# POWER.net
KiCad netlist of a schematic drawn in Altium Designer
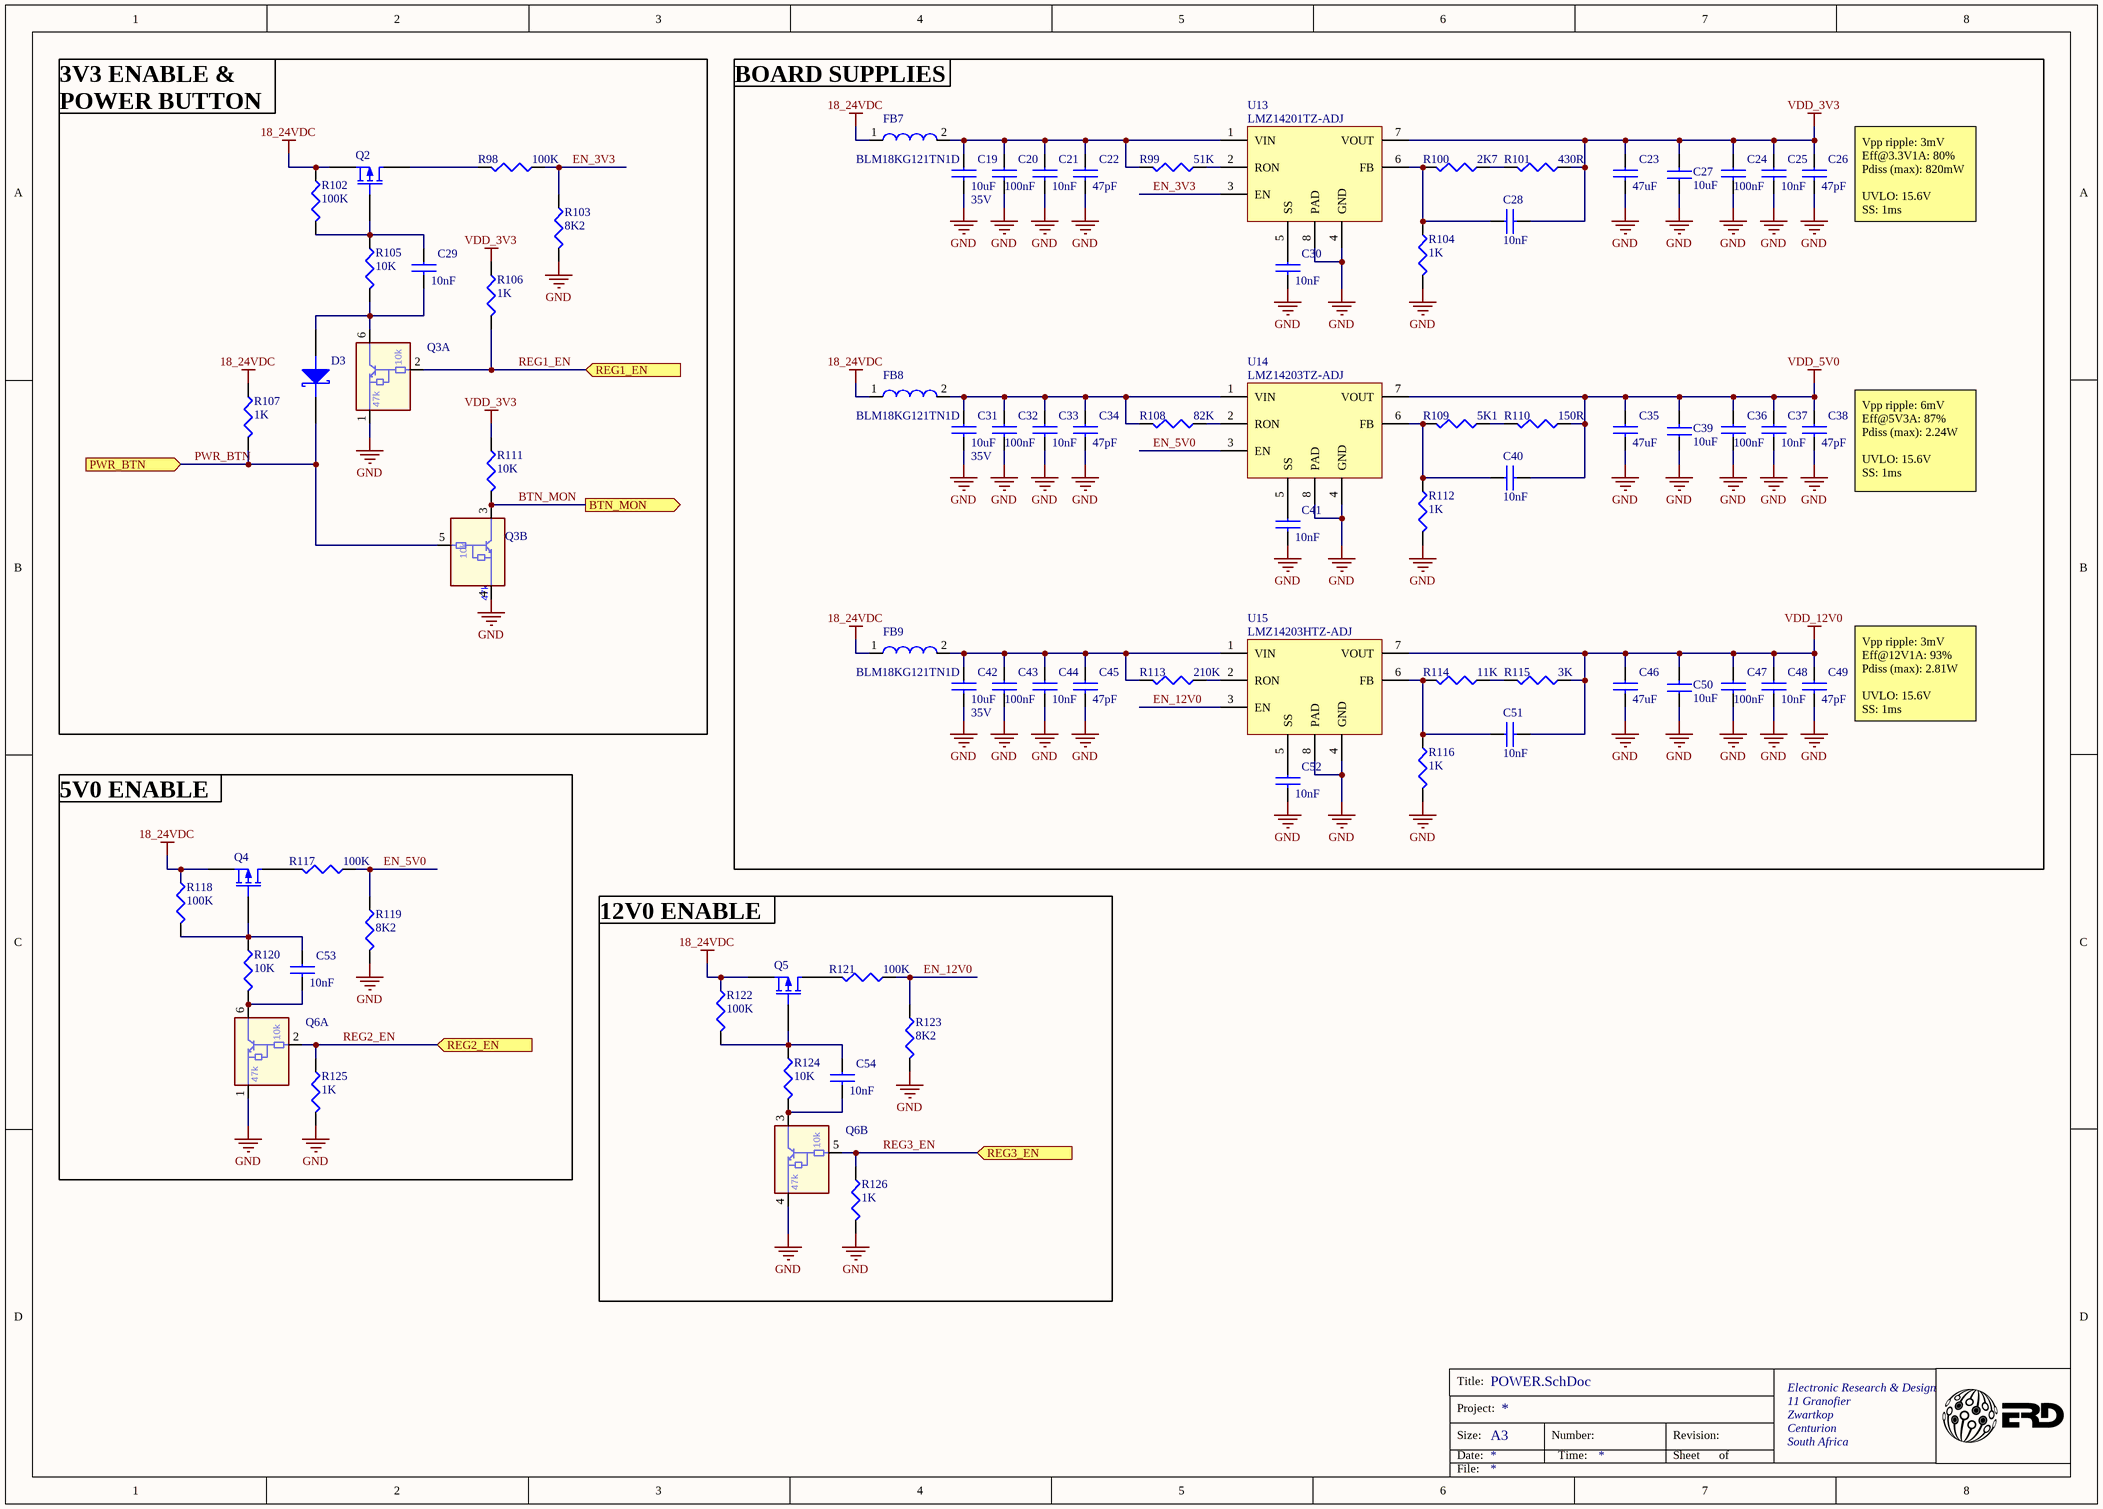
[diagram p0: POWER.SchDoc]

(export (version "E")
  (design (tool "Eeschema 10.0.6"))
  (components
    (comp (ref "C19")
      (value "10uF")
      (footprint "CC0805")
      (description "CAP CER 10UF 35V 10% X5R 0805")
      (fields
        (field (name "MANUFACTURER") "Murata")
        (field (name "PART NUMBER") "GRM21BR6YA106KE43L")
        (field (name "VOLTAGE RATING") "35V")
      )
      (libsource (lib "ERD TiAm") (part "CAP CER 0.1UF 10V 10% X5R 0402"))
    )
    (comp (ref "C20")
      (value "100nF")
      (footprint "CC0402")
      (description "CAP CER 0.1UF 50V 10% X7R 0402")
      (fields (field (name "MANUFACTURER") "Murata") (field (name "PART NUMBER") "GCM155R71H104KE02D"))
      (libsource (lib "ERD TiAm") (part "CAP CER 0.1UF 10V 10% X5R 0402"))
    )
    (comp (ref "C21")
      (value "10nF")
      (footprint "CC0402")
      (description "CAP CER 10NF 50V 10% X7R 0402")
      (fields (field (name "MANUFACTURER") "Murata") (field (name "PART NUMBER") "GRM155R71H103KA88J"))
      (libsource (lib "ERD TiAm") (part "CAP CER 0.1UF 10V 10% X5R 0402"))
    )
    (comp (ref "C22")
      (value "47pF")
      (footprint "CC0402")
      (description "CAP CER 47PF 50V 5% C0G/NP0 0402")
      (fields (field (name "MANUFACTURER") "Murata") (field (name "PART NUMBER") "GCM1555C1H470JA16D"))
      (libsource (lib "ERD TiAm") (part "CAP CER 0.1UF 10V 10% X5R 0402"))
    )
    (comp (ref "C23")
      (value "47uF")
      (footprint "RC1206")
      (description "CAP CER 47UF 25V 20% X5R 1206")
      (fields (field (name "MANUFACTURER") "Murata") (field (name "PART NUMBER") "C3216X5R1E476M160AC"))
      (libsource (lib "ERD TiAm") (part "CAP CER 0.1UF 10V 10% X5R 0402"))
    )
    (comp (ref "C24")
      (value "100nF")
      (footprint "CC0402")
      (description "CAP CER 0.1UF 50V 10% X7R 0402")
      (fields (field (name "MANUFACTURER") "Murata") (field (name "PART NUMBER") "GCM155R71H104KE02D"))
      (libsource (lib "ERD TiAm") (part "CAP CER 0.1UF 10V 10% X5R 0402"))
    )
    (comp (ref "C25")
      (value "10nF")
      (footprint "CC0402")
      (description "CAP CER 10NF 50V 10% X7R 0402")
      (fields (field (name "MANUFACTURER") "Murata") (field (name "PART NUMBER") "GRM155R71H103KA88J"))
      (libsource (lib "ERD TiAm") (part "CAP CER 0.1UF 10V 10% X5R 0402"))
    )
    (comp (ref "C26")
      (value "47pF")
      (footprint "CC0402")
      (description "CAP CER 47PF 50V 5% C0G/NP0 0402")
      (fields (field (name "MANUFACTURER") "Murata") (field (name "PART NUMBER") "GCM1555C1H470JA16D"))
      (libsource (lib "ERD TiAm") (part "CAP CER 0.1UF 10V 10% X5R 0402"))
    )
    (comp (ref "C27")
      (value "10uF")
      (footprint "CC0603")
      (description "CAP CER 10UF 25V 20% X5R 0603")
      (fields (field (name "MANUFACTURER") "Murata") (field (name "PARTNUMBER") "GRM188R61E106MA73D"))
      (libsource (lib "ERD TiAm") (part "CAP CER 0.1UF 10V 10% X5R 0402"))
    )
    (comp (ref "C28")
      (value "10nF")
      (footprint "CC0402")
      (description "CAP CER 10NF 50V 10% X7R 0402")
      (fields (field (name "MANUFACTURER") "Murata") (field (name "PART NUMBER") "GRM155R71H103KA88J"))
      (libsource (lib "ERD TiAm") (part "CAP CER 0.1UF 10V 10% X5R 0402"))
    )
    (comp (ref "C29")
      (value "10nF")
      (footprint "CC0402")
      (description "CAP CER 10NF 50V 10% X7R 0402")
      (fields (field (name "MANUFACTURER") "Murata") (field (name "PART NUMBER") "GRM155R71H103KA88J"))
      (libsource (lib "ERD TiAm") (part "CAP CER 0.1UF 10V 10% X5R 0402"))
    )
    (comp (ref "C30")
      (value "10nF")
      (footprint "CC0402")
      (description "CAP CER 10NF 50V 10% X7R 0402")
      (fields (field (name "MANUFACTURER") "Murata") (field (name "PART NUMBER") "GRM155R71H103KA88J"))
      (libsource (lib "ERD TiAm") (part "CAP CER 0.1UF 10V 10% X5R 0402"))
    )
    (comp (ref "C31")
      (value "10uF")
      (footprint "CC0805")
      (description "CAP CER 10UF 35V 10% X5R 0805")
      (fields
        (field (name "MANUFACTURER") "Murata")
        (field (name "PART NUMBER") "GRM21BR6YA106KE43L")
        (field (name "VOLTAGE RATING") "35V")
      )
      (libsource (lib "ERD TiAm") (part "CAP CER 0.1UF 10V 10% X5R 0402"))
    )
    (comp (ref "C32")
      (value "100nF")
      (footprint "CC0402")
      (description "CAP CER 0.1UF 50V 10% X7R 0402")
      (fields (field (name "MANUFACTURER") "Murata") (field (name "PART NUMBER") "GCM155R71H104KE02D"))
      (libsource (lib "ERD TiAm") (part "CAP CER 0.1UF 10V 10% X5R 0402"))
    )
    (comp (ref "C33")
      (value "10nF")
      (footprint "CC0402")
      (description "CAP CER 10NF 50V 10% X7R 0402")
      (fields (field (name "MANUFACTURER") "Murata") (field (name "PART NUMBER") "GRM155R71H103KA88J"))
      (libsource (lib "ERD TiAm") (part "CAP CER 0.1UF 10V 10% X5R 0402"))
    )
    (comp (ref "C34")
      (value "47pF")
      (footprint "CC0402")
      (description "CAP CER 47PF 50V 5% C0G/NP0 0402")
      (fields (field (name "MANUFACTURER") "Murata") (field (name "PART NUMBER") "GCM1555C1H470JA16D"))
      (libsource (lib "ERD TiAm") (part "CAP CER 0.1UF 10V 10% X5R 0402"))
    )
    (comp (ref "C35")
      (value "47uF")
      (footprint "RC1206")
      (description "CAP CER 47UF 25V 20% X5R 1206")
      (fields (field (name "MANUFACTURER") "Murata") (field (name "PART NUMBER") "C3216X5R1E476M160AC"))
      (libsource (lib "ERD TiAm") (part "CAP CER 0.1UF 10V 10% X5R 0402"))
    )
    (comp (ref "C36")
      (value "100nF")
      (footprint "CC0402")
      (description "CAP CER 0.1UF 50V 10% X7R 0402")
      (fields (field (name "MANUFACTURER") "Murata") (field (name "PART NUMBER") "GCM155R71H104KE02D"))
      (libsource (lib "ERD TiAm") (part "CAP CER 0.1UF 10V 10% X5R 0402"))
    )
    (comp (ref "C37")
      (value "10nF")
      (footprint "CC0402")
      (description "CAP CER 10NF 50V 10% X7R 0402")
      (fields (field (name "MANUFACTURER") "Murata") (field (name "PART NUMBER") "GRM155R71H103KA88J"))
      (libsource (lib "ERD TiAm") (part "CAP CER 0.1UF 10V 10% X5R 0402"))
    )
    (comp (ref "C38")
      (value "47pF")
      (footprint "CC0402")
      (description "CAP CER 47PF 50V 5% C0G/NP0 0402")
      (fields (field (name "MANUFACTURER") "Murata") (field (name "PART NUMBER") "GCM1555C1H470JA16D"))
      (libsource (lib "ERD TiAm") (part "CAP CER 0.1UF 10V 10% X5R 0402"))
    )
    (comp (ref "C39")
      (value "10uF")
      (footprint "CC0603")
      (description "CAP CER 10UF 25V 20% X5R 0603")
      (fields (field (name "MANUFACTURER") "Murata") (field (name "PARTNUMBER") "GRM188R61E106MA73D"))
      (libsource (lib "ERD TiAm") (part "CAP CER 0.1UF 10V 10% X5R 0402"))
    )
    (comp (ref "C40")
      (value "10nF")
      (footprint "CC0402")
      (description "CAP CER 10NF 50V 10% X7R 0402")
      (fields (field (name "MANUFACTURER") "Murata") (field (name "PART NUMBER") "GRM155R71H103KA88J"))
      (libsource (lib "ERD TiAm") (part "CAP CER 0.1UF 10V 10% X5R 0402"))
    )
    (comp (ref "C41")
      (value "10nF")
      (footprint "CC0402")
      (description "CAP CER 10NF 50V 10% X7R 0402")
      (fields (field (name "MANUFACTURER") "Murata") (field (name "PART NUMBER") "GRM155R71H103KA88J"))
      (libsource (lib "ERD TiAm") (part "CAP CER 0.1UF 10V 10% X5R 0402"))
    )
    (comp (ref "C42")
      (value "10uF")
      (footprint "CC0805")
      (description "CAP CER 10UF 35V 10% X5R 0805")
      (fields
        (field (name "MANUFACTURER") "Murata")
        (field (name "PART NUMBER") "GRM21BR6YA106KE43L")
        (field (name "VOLTAGE RATING") "35V")
      )
      (libsource (lib "ERD TiAm") (part "CAP CER 0.1UF 10V 10% X5R 0402"))
    )
    (comp (ref "C43")
      (value "100nF")
      (footprint "CC0402")
      (description "CAP CER 0.1UF 50V 10% X7R 0402")
      (fields (field (name "MANUFACTURER") "Murata") (field (name "PART NUMBER") "GCM155R71H104KE02D"))
      (libsource (lib "ERD TiAm") (part "CAP CER 0.1UF 10V 10% X5R 0402"))
    )
    (comp (ref "C44")
      (value "10nF")
      (footprint "CC0402")
      (description "CAP CER 10NF 50V 10% X7R 0402")
      (fields (field (name "MANUFACTURER") "Murata") (field (name "PART NUMBER") "GRM155R71H103KA88J"))
      (libsource (lib "ERD TiAm") (part "CAP CER 0.1UF 10V 10% X5R 0402"))
    )
    (comp (ref "C45")
      (value "47pF")
      (footprint "CC0402")
      (description "CAP CER 47PF 50V 5% C0G/NP0 0402")
      (fields (field (name "MANUFACTURER") "Murata") (field (name "PART NUMBER") "GCM1555C1H470JA16D"))
      (libsource (lib "ERD TiAm") (part "CAP CER 0.1UF 10V 10% X5R 0402"))
    )
    (comp (ref "C46")
      (value "47uF")
      (footprint "RC1206")
      (description "CAP CER 47UF 25V 20% X5R 1206")
      (fields (field (name "MANUFACTURER") "Murata") (field (name "PART NUMBER") "C3216X5R1E476M160AC"))
      (libsource (lib "ERD TiAm") (part "CAP CER 0.1UF 10V 10% X5R 0402"))
    )
    (comp (ref "C47")
      (value "100nF")
      (footprint "CC0402")
      (description "CAP CER 0.1UF 50V 10% X7R 0402")
      (fields (field (name "MANUFACTURER") "Murata") (field (name "PART NUMBER") "GCM155R71H104KE02D"))
      (libsource (lib "ERD TiAm") (part "CAP CER 0.1UF 10V 10% X5R 0402"))
    )
    (comp (ref "C48")
      (value "10nF")
      (footprint "CC0402")
      (description "CAP CER 10NF 50V 10% X7R 0402")
      (fields (field (name "MANUFACTURER") "Murata") (field (name "PART NUMBER") "GRM155R71H103KA88J"))
      (libsource (lib "ERD TiAm") (part "CAP CER 0.1UF 10V 10% X5R 0402"))
    )
    (comp (ref "C49")
      (value "47pF")
      (footprint "CC0402")
      (description "CAP CER 47PF 50V 5% C0G/NP0 0402")
      (fields (field (name "MANUFACTURER") "Murata") (field (name "PART NUMBER") "GCM1555C1H470JA16D"))
      (libsource (lib "ERD TiAm") (part "CAP CER 0.1UF 10V 10% X5R 0402"))
    )
    (comp (ref "C50")
      (value "10uF")
      (footprint "CC0603")
      (description "CAP CER 10UF 25V 20% X5R 0603")
      (fields (field (name "MANUFACTURER") "Murata") (field (name "PARTNUMBER") "GRM188R61E106MA73D"))
      (libsource (lib "ERD TiAm") (part "CAP CER 0.1UF 10V 10% X5R 0402"))
    )
    (comp (ref "C51")
      (value "10nF")
      (footprint "CC0402")
      (description "CAP CER 10NF 50V 10% X7R 0402")
      (fields (field (name "MANUFACTURER") "Murata") (field (name "PART NUMBER") "GRM155R71H103KA88J"))
      (libsource (lib "ERD TiAm") (part "CAP CER 0.1UF 10V 10% X5R 0402"))
    )
    (comp (ref "C52")
      (value "10nF")
      (footprint "CC0402")
      (description "CAP CER 10NF 50V 10% X7R 0402")
      (fields (field (name "MANUFACTURER") "Murata") (field (name "PART NUMBER") "GRM155R71H103KA88J"))
      (libsource (lib "ERD TiAm") (part "CAP CER 0.1UF 10V 10% X5R 0402"))
    )
    (comp (ref "C53")
      (value "10nF")
      (footprint "CC0402")
      (description "CAP CER 10NF 50V 10% X7R 0402")
      (fields (field (name "MANUFACTURER") "Murata") (field (name "PART NUMBER") "GRM155R71H103KA88J"))
      (libsource (lib "ERD TiAm") (part "CAP CER 0.1UF 10V 10% X5R 0402"))
    )
    (comp (ref "C54")
      (value "10nF")
      (footprint "CC0402")
      (description "CAP CER 10NF 50V 10% X7R 0402")
      (fields (field (name "MANUFACTURER") "Murata") (field (name "PART NUMBER") "GRM155R71H103KA88J"))
      (libsource (lib "ERD TiAm") (part "CAP CER 0.1UF 10V 10% X5R 0402"))
    )
    (comp (ref "D3")
      (value "PMEG10020ELRX")
      (footprint "SOD123W")
      (description "DIODE, SCHOTTKY, 100V, 2A, 3.7ns, SOD123W")
      (libsource (lib "GadgetJD") (part "DIODE SCHOTTKY"))
    )
    (comp (ref "FB7")
      (value "BLM18KG121TN1D")
      (footprint "LC0603")
      (description "FERRITE 3A 30mOHM 0603 SMD")
      (libsource (lib "BEAGLEBONEBLACK_REV A5B") (part "FER_180_200_0"))
    )
    (comp (ref "FB8")
      (value "BLM18KG121TN1D")
      (footprint "LC0603")
      (description "FERRITE 3A 30mOHM 0603 SMD")
      (libsource (lib "BEAGLEBONEBLACK_REV A5B") (part "FER_180_200_0"))
    )
    (comp (ref "FB9")
      (value "BLM18KG121TN1D")
      (footprint "LC0603")
      (description "FERRITE 3A 30mOHM 0603 SMD")
      (libsource (lib "BEAGLEBONEBLACK_REV A5B") (part "FER_180_200_0"))
    )
    (comp (ref "Q2")
      (value "MOSFET-P")
      (footprint "E3")
      (description "P-Channel MOSFET")
      (fields (field (name "PUBLISHER") "Altium Limited"))
      (libsource (lib "Miscellaneous Devices") (part "MOSFET-P"))
    )
    (comp (ref "Q3")
      (value "DDC114YU-7-F")
      (description "TRANS PREBIASED DUAL NPN SOT363")
      (fields (field (name "MANUFACTURER") "Diodes Inc"))
      (libsource (lib "") (part "RN1907_1"))
    )
    (comp (ref "Q4")
      (value "MOSFET-P")
      (footprint "E3")
      (description "P-Channel MOSFET")
      (fields (field (name "PUBLISHER") "Altium Limited"))
      (libsource (lib "Miscellaneous Devices") (part "MOSFET-P"))
    )
    (comp (ref "Q5")
      (value "MOSFET-P")
      (footprint "E3")
      (description "P-Channel MOSFET")
      (fields (field (name "PUBLISHER") "Altium Limited"))
      (libsource (lib "Miscellaneous Devices") (part "MOSFET-P"))
    )
    (comp (ref "Q6")
      (value "DDC114YU-7-F")
      (description "TRANS PREBIASED DUAL NPN SOT363")
      (fields (field (name "MANUFACTURER") "Diodes Inc"))
      (libsource (lib "ERD TiAm") (part "RN1907"))
    )
    (comp (ref "R98")
      (value "100K")
      (footprint "RC0402")
      (description "RES, 100K OHM, 1/16W, 1%, 0402")
      (fields (field (name "MANUFACTURER") "Yageo") (field (name "PARTNUMBER") "RC0402FR-07100KL"))
      (libsource (lib "ERD TiAm") (part "RES_10K_1/16W_1%_0402"))
    )
    (comp (ref "R99")
      (value "51K")
      (footprint "RC0402")
      (description "RES, 51K OHM, 1/16W, 1%, 0402")
      (fields (field (name "MANUFACTURER") "Yageo") (field (name "PARTNUMBER") "RC0402FR-0751KL"))
      (libsource (lib "ERD TiAm") (part "RES_10K_1/16W_1%_0402"))
    )
    (comp (ref "R100")
      (value "2K7")
      (footprint "RC0402")
      (description "RES, 2K7 OHM, 1/16W, 1%, 0402")
      (fields (field (name "MANUFACTURER") "Yageo") (field (name "PARTNUMBER") "RC0402FR-072K7L"))
      (libsource (lib "ERD TiAm") (part "RES_10K_1/16W_1%_0402"))
    )
    (comp (ref "R101")
      (value "430R")
      (footprint "RC0402")
      (description "RES, 430 OHM, 1/16W, 1%, 0402")
      (fields (field (name "MANUFACTURER") "Yageo") (field (name "PARTNUMBER") "RC0402FR-07430RL"))
      (libsource (lib "ERD TiAm") (part "RES_10K_1/16W_1%_0402"))
    )
    (comp (ref "R102")
      (value "100K")
      (footprint "RC0402")
      (description "RES, 100K OHM, 1/16W, 1%, 0402")
      (fields (field (name "MANUFACTURER") "Yageo") (field (name "PART NUMBER") "RC0402FR-07100KL"))
      (libsource (lib "ERD TiAm") (part "RES_10K_1/16W_1%_0402"))
    )
    (comp (ref "R103")
      (value "8K2")
      (footprint "RC0402")
      (description "RES, 8K2 OHM, 1/16W, 1%, 0402")
      (fields (field (name "MANUFACTURER") "Yageo") (field (name "PARTNUMBER") "RC0402FR-078K2L"))
      (libsource (lib "ERD TiAm") (part "RES_10K_1/16W_1%_0402"))
    )
    (comp (ref "R104")
      (value "1K")
      (footprint "RC0402")
      (description "RES, 1K OHM, 1/16W, 1%, 0402")
      (fields (field (name "MANUFACTURER") "Yageo") (field (name "PARTNUMBER") "RC0402FR-071KL"))
      (libsource (lib "ERD TiAm") (part "RES_10K_1/16W_1%_0402"))
    )
    (comp (ref "R105")
      (value "10K")
      (footprint "RC0402")
      (description "RES, 10K OHM, 1/16W, 1%, 0402")
      (fields (field (name "MANUFACTURER") "Yageo") (field (name "PART NUMBER") "RC0402FR-0710KL"))
      (libsource (lib "ERD TiAm") (part "RES_10K_1/16W_1%_0402"))
    )
    (comp (ref "R106")
      (value "1K")
      (footprint "RC0402")
      (description "RES, 1K OHM, 1/16W, 1%, 0402")
      (fields (field (name "MANUFACTURER") "Yageo") (field (name "PARTNUMBER") "RC0402FR-071KL"))
      (libsource (lib "ERD TiAm") (part "RES_10K_1/16W_1%_0402"))
    )
    (comp (ref "R107")
      (value "1K")
      (footprint "RC0402")
      (description "RES, 1K OHM, 1/16W, 1%, 0402")
      (fields (field (name "MANUFACTURER") "Yageo") (field (name "PARTNUMBER") "RC0402FR-071KL"))
      (libsource (lib "ERD TiAm") (part "RES_10K_1/16W_1%_0402"))
    )
    (comp (ref "R108")
      (value "82K")
      (footprint "RC0402")
      (description "RES, 82K OHM, 1/16W, 1%, 0402")
      (fields (field (name "MANUFACTURER") "Yageo") (field (name "PARTNUMBER") "RC0402FR-0782KL"))
      (libsource (lib "ERD TiAm") (part "RES_10K_1/16W_1%_0402"))
    )
    (comp (ref "R109")
      (value "5K1")
      (footprint "RC0402")
      (description "RES, 5K1 OHM, 1/16W, 1%, 0402")
      (fields (field (name "MANUFACTURER") "Yageo") (field (name "PARTNUMBER") "RC0402FR-075K1L"))
      (libsource (lib "ERD TiAm") (part "RES_10K_1/16W_1%_0402"))
    )
    (comp (ref "R110")
      (value "150R")
      (footprint "RC0402")
      (description "RES, 150 OHM, 1/16W, 1%, 0402")
      (fields (field (name "MANUFACTURER") "Yageo") (field (name "PARTNUMBER") "RC0402FR-07150RL"))
      (libsource (lib "ERD TiAm") (part "RES_10K_1/16W_1%_0402"))
    )
    (comp (ref "R111")
      (value "10K")
      (footprint "RC0402")
      (description "RES, 10K OHM, 1/16W, 1%, 0402")
      (fields (field (name "MANUFACTURER") "Yageo") (field (name "PART NUMBER") "RC0402FR-0710KL"))
      (libsource (lib "ERD TiAm") (part "RES_10K_1/16W_1%_0402"))
    )
    (comp (ref "R112")
      (value "1K")
      (footprint "RC0402")
      (description "RES, 1K OHM, 1/16W, 1%, 0402")
      (fields (field (name "MANUFACTURER") "Yageo") (field (name "PARTNUMBER") "RC0402FR-071KL"))
      (libsource (lib "ERD TiAm") (part "RES_10K_1/16W_1%_0402"))
    )
    (comp (ref "R113")
      (value "210K")
      (footprint "RC0402")
      (description "RES, 210K OHM, 1/16W, 1%, 0402")
      (fields (field (name "MANUFACTURER") "Yageo") (field (name "PARTNUMBER") "RC0402FR-07210KL"))
      (libsource (lib "ERD TiAm") (part "RES_10K_1/16W_1%_0402"))
    )
    (comp (ref "R114")
      (value "11K")
      (footprint "RC0402")
      (description "RES, 11K OHM, 1/16W, 1%, 0402")
      (fields (field (name "MANUFACTURER") "Yageo") (field (name "PARTNUMBER") "RC0402FR-0711KL"))
      (libsource (lib "ERD TiAm") (part "RES_10K_1/16W_1%_0402"))
    )
    (comp (ref "R115")
      (value "3K")
      (footprint "RC0402")
      (description "RES, 3K OHM, 1/16W, 1%, 0402")
      (fields (field (name "MANUFACTURER") "Yageo") (field (name "PARTNUMBER") "RC0402FR-073KL"))
      (libsource (lib "ERD TiAm") (part "RES_10K_1/16W_1%_0402"))
    )
    (comp (ref "R116")
      (value "1K")
      (footprint "RC0402")
      (description "RES, 1K OHM, 1/16W, 1%, 0402")
      (fields (field (name "MANUFACTURER") "Yageo") (field (name "PARTNUMBER") "RC0402FR-071KL"))
      (libsource (lib "ERD TiAm") (part "RES_10K_1/16W_1%_0402"))
    )
    (comp (ref "R117")
      (value "100K")
      (footprint "RC0402")
      (description "RES, 100K OHM, 1/16W, 1%, 0402")
      (fields (field (name "MANUFACTURER") "Yageo") (field (name "PARTNUMBER") "RC0402FR-07100KL"))
      (libsource (lib "ERD TiAm") (part "RES_10K_1/16W_1%_0402"))
    )
    (comp (ref "R118")
      (value "100K")
      (footprint "RC0402")
      (description "RES, 100K OHM, 1/16W, 1%, 0402")
      (fields (field (name "MANUFACTURER") "Yageo") (field (name "PART NUMBER") "RC0402FR-07100KL"))
      (libsource (lib "ERD TiAm") (part "RES_10K_1/16W_1%_0402"))
    )
    (comp (ref "R119")
      (value "8K2")
      (footprint "RC0402")
      (description "RES, 8K2 OHM, 1/16W, 1%, 0402")
      (fields (field (name "MANUFACTURER") "Yageo") (field (name "PARTNUMBER") "RC0402FR-078K2L"))
      (libsource (lib "ERD TiAm") (part "RES_10K_1/16W_1%_0402"))
    )
    (comp (ref "R120")
      (value "10K")
      (footprint "RC0402")
      (description "RES, 10K OHM, 1/16W, 1%, 0402")
      (fields (field (name "MANUFACTURER") "Yageo") (field (name "PART NUMBER") "RC0402FR-0710KL"))
      (libsource (lib "ERD TiAm") (part "RES_10K_1/16W_1%_0402"))
    )
    (comp (ref "R121")
      (value "100K")
      (footprint "RC0402")
      (description "RES, 100K OHM, 1/16W, 1%, 0402")
      (fields (field (name "MANUFACTURER") "Yageo") (field (name "PARTNUMBER") "RC0402FR-07100KL"))
      (libsource (lib "ERD TiAm") (part "RES_10K_1/16W_1%_0402"))
    )
    (comp (ref "R122")
      (value "100K")
      (footprint "RC0402")
      (description "RES, 100K OHM, 1/16W, 1%, 0402")
      (fields (field (name "MANUFACTURER") "Yageo") (field (name "PART NUMBER") "RC0402FR-07100KL"))
      (libsource (lib "ERD TiAm") (part "RES_10K_1/16W_1%_0402"))
    )
    (comp (ref "R123")
      (value "8K2")
      (footprint "RC0402")
      (description "RES, 8K2 OHM, 1/16W, 1%, 0402")
      (fields (field (name "MANUFACTURER") "Yageo") (field (name "PARTNUMBER") "RC0402FR-078K2L"))
      (libsource (lib "ERD TiAm") (part "RES_10K_1/16W_1%_0402"))
    )
    (comp (ref "R124")
      (value "10K")
      (footprint "RC0402")
      (description "RES, 10K OHM, 1/16W, 1%, 0402")
      (fields (field (name "MANUFACTURER") "Yageo") (field (name "PART NUMBER") "RC0402FR-0710KL"))
      (libsource (lib "ERD TiAm") (part "RES_10K_1/16W_1%_0402"))
    )
    (comp (ref "R125")
      (value "1K")
      (footprint "RC0402")
      (description "RES, 1K OHM, 1/16W, 1%, 0402")
      (fields (field (name "MANUFACTURER") "Yageo") (field (name "PARTNUMBER") "RC0402FR-071KL"))
      (libsource (lib "ERD TiAm") (part "RES_10K_1/16W_1%_0402"))
    )
    (comp (ref "R126")
      (value "1K")
      (footprint "RC0402")
      (description "RES, 1K OHM, 1/16W, 1%, 0402")
      (fields (field (name "MANUFACTURER") "Yageo") (field (name "PARTNUMBER") "RC0402FR-071KL"))
      (libsource (lib "ERD TiAm") (part "RES_10K_1/16W_1%_0402"))
    )
    (comp (ref "U13")
      (value "LMZ14201TZ-ADJ")
      (footprint "TZA07A")
      (description "Buc Converter, SimpleSwitcher, 42V, 1A, TO-PMOD-7")
      (fields (field (name "MANUFACTURER") "Texas Instruments"))
      (libsource (lib "ERD TiAm") (part "LMZ14201"))
    )
    (comp (ref "U14")
      (value "LMZ14203TZ-ADJ")
      (footprint "TZA07A")
      (description "Buc Converter, SimpleSwitcher, 42V, 1A, TO-PMOD-7")
      (fields (field (name "MANUFACTURER") "Texas Instruments"))
      (libsource (lib "ERD TiAm") (part "LMZ14201"))
    )
    (comp (ref "U15")
      (value "LMZ14203HTZ-ADJ")
      (footprint "TZA07A")
      (description "Buc Converter, SimpleSwitcher, 42V, 1A, TO-PMOD-7")
      (fields (field (name "MANUFACTURER") "Texas Instruments"))
      (libsource (lib "ERD TiAm") (part "LMZ14201"))
    )
  )
  (nets
    (net (code "1") (name "/BTN_MON") (class "Default")
      (node (ref "Q3") (pin "3") (pinfunction "3_3") (pintype "passive"))
      (node (ref "R111") (pin "2") (pinfunction "2_2") (pintype "passive"))
    )
    (net (code "2") (name "/EN_3V3") (class "Default")
      (node (ref "R103") (pin "1") (pinfunction "1_1") (pintype "passive"))
      (node (ref "R98") (pin "1") (pinfunction "1_1") (pintype "passive"))
      (node (ref "U13") (pin "3") (pinfunction "EN_3") (pintype "power_in"))
    )
    (net (code "3") (name "/EN_5V0") (class "Default")
      (node (ref "R117") (pin "1") (pinfunction "1_1") (pintype "passive"))
      (node (ref "R119") (pin "1") (pinfunction "1_1") (pintype "passive"))
      (node (ref "U14") (pin "3") (pinfunction "EN_3") (pintype "power_in"))
    )
    (net (code "4") (name "/EN_12V0") (class "Default")
      (node (ref "R121") (pin "1") (pinfunction "1_1") (pintype "passive"))
      (node (ref "R123") (pin "1") (pinfunction "1_1") (pintype "passive"))
      (node (ref "U15") (pin "3") (pinfunction "EN_3") (pintype "power_in"))
    )
    (net (code "5") (name "/PWR_BTN") (class "Default")
      (node (ref "D3") (pin "1") (pinfunction "1_1") (pintype "passive"))
      (node (ref "Q3") (pin "5") (pinfunction "5_5") (pintype "passive"))
      (node (ref "R107") (pin "2") (pinfunction "2_2") (pintype "passive"))
    )
    (net (code "6") (name "/REG1_EN") (class "Default")
      (node (ref "Q3") (pin "2") (pinfunction "5_2") (pintype "passive"))
      (node (ref "R106") (pin "2") (pinfunction "2_2") (pintype "passive"))
    )
    (net (code "7") (name "/REG2_EN") (class "Default")
      (node (ref "Q6") (pin "2") (pinfunction "5_2") (pintype "passive"))
      (node (ref "R125") (pin "1") (pinfunction "1_1") (pintype "passive"))
    )
    (net (code "8") (name "/REG3_EN") (class "Default")
      (node (ref "Q6") (pin "5") (pinfunction "5_5") (pintype "passive"))
      (node (ref "R126") (pin "1") (pinfunction "1_1") (pintype "passive"))
    )
    (net (code "9") (name "18_24VDC") (class "Default")
      (node (ref "FB7") (pin "1") (pinfunction "1_1") (pintype "passive"))
      (node (ref "FB8") (pin "1") (pinfunction "1_1") (pintype "passive"))
      (node (ref "FB9") (pin "1") (pinfunction "1_1") (pintype "passive"))
      (node (ref "Q2") (pin "3") (pinfunction "S_3") (pintype "passive"))
      (node (ref "Q4") (pin "3") (pinfunction "S_3") (pintype "passive"))
      (node (ref "Q5") (pin "3") (pinfunction "S_3") (pintype "passive"))
      (node (ref "R102") (pin "1") (pinfunction "1_1") (pintype "passive"))
      (node (ref "R107") (pin "1") (pinfunction "1_1") (pintype "passive"))
      (node (ref "R118") (pin "1") (pinfunction "1_1") (pintype "passive"))
      (node (ref "R122") (pin "1") (pinfunction "1_1") (pintype "passive"))
    )
    (net (code "10") (name "GND") (class "Default")
      (node (ref "C19") (pin "2") (pinfunction "2_2") (pintype "passive"))
      (node (ref "C20") (pin "2") (pinfunction "2_2") (pintype "passive"))
      (node (ref "C21") (pin "2") (pinfunction "2_2") (pintype "passive"))
      (node (ref "C22") (pin "2") (pinfunction "2_2") (pintype "passive"))
      (node (ref "C23") (pin "2") (pinfunction "2_2") (pintype "passive"))
      (node (ref "C24") (pin "2") (pinfunction "2_2") (pintype "passive"))
      (node (ref "C25") (pin "2") (pinfunction "2_2") (pintype "passive"))
      (node (ref "C26") (pin "2") (pinfunction "2_2") (pintype "passive"))
      (node (ref "C27") (pin "1") (pinfunction "1_1") (pintype "passive"))
      (node (ref "C30") (pin "2") (pinfunction "2_2") (pintype "passive"))
      (node (ref "C31") (pin "2") (pinfunction "2_2") (pintype "passive"))
      (node (ref "C32") (pin "2") (pinfunction "2_2") (pintype "passive"))
      (node (ref "C33") (pin "2") (pinfunction "2_2") (pintype "passive"))
      (node (ref "C34") (pin "2") (pinfunction "2_2") (pintype "passive"))
      (node (ref "C35") (pin "2") (pinfunction "2_2") (pintype "passive"))
      (node (ref "C36") (pin "2") (pinfunction "2_2") (pintype "passive"))
      (node (ref "C37") (pin "2") (pinfunction "2_2") (pintype "passive"))
      (node (ref "C38") (pin "2") (pinfunction "2_2") (pintype "passive"))
      (node (ref "C39") (pin "1") (pinfunction "1_1") (pintype "passive"))
      (node (ref "C41") (pin "2") (pinfunction "2_2") (pintype "passive"))
      (node (ref "C42") (pin "2") (pinfunction "2_2") (pintype "passive"))
      (node (ref "C43") (pin "2") (pinfunction "2_2") (pintype "passive"))
      (node (ref "C44") (pin "2") (pinfunction "2_2") (pintype "passive"))
      (node (ref "C45") (pin "2") (pinfunction "2_2") (pintype "passive"))
      (node (ref "C46") (pin "2") (pinfunction "2_2") (pintype "passive"))
      (node (ref "C47") (pin "2") (pinfunction "2_2") (pintype "passive"))
      (node (ref "C48") (pin "2") (pinfunction "2_2") (pintype "passive"))
      (node (ref "C49") (pin "2") (pinfunction "2_2") (pintype "passive"))
      (node (ref "C50") (pin "1") (pinfunction "1_1") (pintype "passive"))
      (node (ref "C52") (pin "2") (pinfunction "2_2") (pintype "passive"))
      (node (ref "Q3") (pin "1") (pinfunction "4_1") (pintype "passive"))
      (node (ref "Q3") (pin "4") (pinfunction "4_4") (pintype "passive"))
      (node (ref "Q6") (pin "1") (pinfunction "4_1") (pintype "passive"))
      (node (ref "Q6") (pin "4") (pinfunction "4_4") (pintype "passive"))
      (node (ref "R103") (pin "2") (pinfunction "2_2") (pintype "passive"))
      (node (ref "R104") (pin "2") (pinfunction "2_2") (pintype "passive"))
      (node (ref "R112") (pin "2") (pinfunction "2_2") (pintype "passive"))
      (node (ref "R116") (pin "2") (pinfunction "2_2") (pintype "passive"))
      (node (ref "R119") (pin "2") (pinfunction "2_2") (pintype "passive"))
      (node (ref "R123") (pin "2") (pinfunction "2_2") (pintype "passive"))
      (node (ref "R125") (pin "2") (pinfunction "2_2") (pintype "passive"))
      (node (ref "R126") (pin "2") (pinfunction "2_2") (pintype "passive"))
      (node (ref "U13") (pin "4") (pinfunction "GND_4") (pintype "power_in"))
      (node (ref "U13") (pin "8") (pinfunction "PAD_8") (pintype "power_in"))
      (node (ref "U14") (pin "4") (pinfunction "GND_4") (pintype "power_in"))
      (node (ref "U14") (pin "8") (pinfunction "PAD_8") (pintype "power_in"))
      (node (ref "U15") (pin "4") (pinfunction "GND_4") (pintype "power_in"))
      (node (ref "U15") (pin "8") (pinfunction "PAD_8") (pintype "power_in"))
    )
    (net (code "11") (name "Net-(C54-Pad2)") (class "Default")
      (node (ref "C54") (pin "2") (pinfunction "2_2") (pintype "passive"))
      (node (ref "Q6") (pin "3") (pinfunction "3_3") (pintype "passive"))
      (node (ref "R124") (pin "2") (pinfunction "2_2") (pintype "passive"))
    )
    (net (code "12") (name "Net-(Q2-D)") (class "Default")
      (node (ref "Q2") (pin "1") (pinfunction "D_1") (pintype "passive"))
      (node (ref "R98") (pin "2") (pinfunction "2_2") (pintype "passive"))
    )
    (net (code "13") (name "Net-(Q2-G)") (class "Default")
      (node (ref "C29") (pin "1") (pinfunction "1_1") (pintype "passive"))
      (node (ref "Q2") (pin "2") (pinfunction "G_2") (pintype "passive"))
      (node (ref "R102") (pin "2") (pinfunction "2_2") (pintype "passive"))
      (node (ref "R105") (pin "1") (pinfunction "1_1") (pintype "passive"))
    )
    (net (code "14") (name "Net-(Q3A-3)") (class "Default")
      (node (ref "C29") (pin "2") (pinfunction "2_2") (pintype "passive"))
      (node (ref "D3") (pin "2") (pinfunction "2_2") (pintype "passive"))
      (node (ref "Q3") (pin "6") (pinfunction "3_6") (pintype "passive"))
      (node (ref "R105") (pin "2") (pinfunction "2_2") (pintype "passive"))
    )
    (net (code "15") (name "Net-(Q4-D)") (class "Default")
      (node (ref "Q4") (pin "1") (pinfunction "D_1") (pintype "passive"))
      (node (ref "R117") (pin "2") (pinfunction "2_2") (pintype "passive"))
    )
    (net (code "16") (name "Net-(Q4-G)") (class "Default")
      (node (ref "C53") (pin "1") (pinfunction "1_1") (pintype "passive"))
      (node (ref "Q4") (pin "2") (pinfunction "G_2") (pintype "passive"))
      (node (ref "R118") (pin "2") (pinfunction "2_2") (pintype "passive"))
      (node (ref "R120") (pin "1") (pinfunction "1_1") (pintype "passive"))
    )
    (net (code "17") (name "Net-(Q5-D)") (class "Default")
      (node (ref "Q5") (pin "1") (pinfunction "D_1") (pintype "passive"))
      (node (ref "R121") (pin "2") (pinfunction "2_2") (pintype "passive"))
    )
    (net (code "18") (name "Net-(Q5-G)") (class "Default")
      (node (ref "C54") (pin "1") (pinfunction "1_1") (pintype "passive"))
      (node (ref "Q5") (pin "2") (pinfunction "G_2") (pintype "passive"))
      (node (ref "R122") (pin "2") (pinfunction "2_2") (pintype "passive"))
      (node (ref "R124") (pin "1") (pinfunction "1_1") (pintype "passive"))
    )
    (net (code "19") (name "Net-(Q6A-3)") (class "Default")
      (node (ref "C53") (pin "2") (pinfunction "2_2") (pintype "passive"))
      (node (ref "Q6") (pin "6") (pinfunction "3_6") (pintype "passive"))
      (node (ref "R120") (pin "2") (pinfunction "2_2") (pintype "passive"))
    )
    (net (code "20") (name "Net-(R100-Pad1)") (class "Default")
      (node (ref "R100") (pin "1") (pinfunction "1_1") (pintype "passive"))
      (node (ref "R101") (pin "2") (pinfunction "2_2") (pintype "passive"))
    )
    (net (code "21") (name "Net-(R109-Pad1)") (class "Default")
      (node (ref "R109") (pin "1") (pinfunction "1_1") (pintype "passive"))
      (node (ref "R110") (pin "2") (pinfunction "2_2") (pintype "passive"))
    )
    (net (code "22") (name "Net-(R114-Pad1)") (class "Default")
      (node (ref "R114") (pin "1") (pinfunction "1_1") (pintype "passive"))
      (node (ref "R115") (pin "2") (pinfunction "2_2") (pintype "passive"))
    )
    (net (code "23") (name "Net-(U13-FB)") (class "Default")
      (node (ref "C28") (pin "1") (pinfunction "1_1") (pintype "passive"))
      (node (ref "R100") (pin "2") (pinfunction "2_2") (pintype "passive"))
      (node (ref "R104") (pin "1") (pinfunction "1_1") (pintype "passive"))
      (node (ref "U13") (pin "6") (pinfunction "FB_6") (pintype "power_in"))
    )
    (net (code "24") (name "Net-(U13-RON)") (class "Default")
      (node (ref "R99") (pin "1") (pinfunction "1_1") (pintype "passive"))
      (node (ref "U13") (pin "2") (pinfunction "RON_2") (pintype "power_in"))
    )
    (net (code "25") (name "Net-(U13-SS)") (class "Default")
      (node (ref "C30") (pin "1") (pinfunction "1_1") (pintype "passive"))
      (node (ref "U13") (pin "5") (pinfunction "SS_5") (pintype "power_in"))
    )
    (net (code "26") (name "Net-(U13-VIN)") (class "Default")
      (node (ref "C19") (pin "1") (pinfunction "1_1") (pintype "passive"))
      (node (ref "C20") (pin "1") (pinfunction "1_1") (pintype "passive"))
      (node (ref "C21") (pin "1") (pinfunction "1_1") (pintype "passive"))
      (node (ref "C22") (pin "1") (pinfunction "1_1") (pintype "passive"))
      (node (ref "FB7") (pin "2") (pinfunction "2_2") (pintype "passive"))
      (node (ref "R99") (pin "2") (pinfunction "2_2") (pintype "passive"))
      (node (ref "U13") (pin "1") (pinfunction "VIN_1") (pintype "power_in"))
    )
    (net (code "27") (name "Net-(U14-FB)") (class "Default")
      (node (ref "C40") (pin "1") (pinfunction "1_1") (pintype "passive"))
      (node (ref "R109") (pin "2") (pinfunction "2_2") (pintype "passive"))
      (node (ref "R112") (pin "1") (pinfunction "1_1") (pintype "passive"))
      (node (ref "U14") (pin "6") (pinfunction "FB_6") (pintype "power_in"))
    )
    (net (code "28") (name "Net-(U14-RON)") (class "Default")
      (node (ref "R108") (pin "1") (pinfunction "1_1") (pintype "passive"))
      (node (ref "U14") (pin "2") (pinfunction "RON_2") (pintype "power_in"))
    )
    (net (code "29") (name "Net-(U14-SS)") (class "Default")
      (node (ref "C41") (pin "1") (pinfunction "1_1") (pintype "passive"))
      (node (ref "U14") (pin "5") (pinfunction "SS_5") (pintype "power_in"))
    )
    (net (code "30") (name "Net-(U14-VIN)") (class "Default")
      (node (ref "C31") (pin "1") (pinfunction "1_1") (pintype "passive"))
      (node (ref "C32") (pin "1") (pinfunction "1_1") (pintype "passive"))
      (node (ref "C33") (pin "1") (pinfunction "1_1") (pintype "passive"))
      (node (ref "C34") (pin "1") (pinfunction "1_1") (pintype "passive"))
      (node (ref "FB8") (pin "2") (pinfunction "2_2") (pintype "passive"))
      (node (ref "R108") (pin "2") (pinfunction "2_2") (pintype "passive"))
      (node (ref "U14") (pin "1") (pinfunction "VIN_1") (pintype "power_in"))
    )
    (net (code "31") (name "Net-(U15-FB)") (class "Default")
      (node (ref "C51") (pin "1") (pinfunction "1_1") (pintype "passive"))
      (node (ref "R114") (pin "2") (pinfunction "2_2") (pintype "passive"))
      (node (ref "R116") (pin "1") (pinfunction "1_1") (pintype "passive"))
      (node (ref "U15") (pin "6") (pinfunction "FB_6") (pintype "power_in"))
    )
    (net (code "32") (name "Net-(U15-RON)") (class "Default")
      (node (ref "R113") (pin "1") (pinfunction "1_1") (pintype "passive"))
      (node (ref "U15") (pin "2") (pinfunction "RON_2") (pintype "power_in"))
    )
    (net (code "33") (name "Net-(U15-SS)") (class "Default")
      (node (ref "C52") (pin "1") (pinfunction "1_1") (pintype "passive"))
      (node (ref "U15") (pin "5") (pinfunction "SS_5") (pintype "power_in"))
    )
    (net (code "34") (name "Net-(U15-VIN)") (class "Default")
      (node (ref "C42") (pin "1") (pinfunction "1_1") (pintype "passive"))
      (node (ref "C43") (pin "1") (pinfunction "1_1") (pintype "passive"))
      (node (ref "C44") (pin "1") (pinfunction "1_1") (pintype "passive"))
      (node (ref "C45") (pin "1") (pinfunction "1_1") (pintype "passive"))
      (node (ref "FB9") (pin "2") (pinfunction "2_2") (pintype "passive"))
      (node (ref "R113") (pin "2") (pinfunction "2_2") (pintype "passive"))
      (node (ref "U15") (pin "1") (pinfunction "VIN_1") (pintype "power_in"))
    )
    (net (code "35") (name "VDD_3V3") (class "Default")
      (node (ref "C23") (pin "1") (pinfunction "1_1") (pintype "passive"))
      (node (ref "C24") (pin "1") (pinfunction "1_1") (pintype "passive"))
      (node (ref "C25") (pin "1") (pinfunction "1_1") (pintype "passive"))
      (node (ref "C26") (pin "1") (pinfunction "1_1") (pintype "passive"))
      (node (ref "C27") (pin "2") (pinfunction "2_2") (pintype "passive"))
      (node (ref "C28") (pin "2") (pinfunction "2_2") (pintype "passive"))
      (node (ref "R101") (pin "1") (pinfunction "1_1") (pintype "passive"))
      (node (ref "R106") (pin "1") (pinfunction "1_1") (pintype "passive"))
      (node (ref "R111") (pin "1") (pinfunction "1_1") (pintype "passive"))
      (node (ref "U13") (pin "7") (pinfunction "VOUT_7") (pintype "power_in"))
    )
    (net (code "36") (name "VDD_5V0") (class "Default")
      (node (ref "C35") (pin "1") (pinfunction "1_1") (pintype "passive"))
      (node (ref "C36") (pin "1") (pinfunction "1_1") (pintype "passive"))
      (node (ref "C37") (pin "1") (pinfunction "1_1") (pintype "passive"))
      (node (ref "C38") (pin "1") (pinfunction "1_1") (pintype "passive"))
      (node (ref "C39") (pin "2") (pinfunction "2_2") (pintype "passive"))
      (node (ref "C40") (pin "2") (pinfunction "2_2") (pintype "passive"))
      (node (ref "R110") (pin "1") (pinfunction "1_1") (pintype "passive"))
      (node (ref "U14") (pin "7") (pinfunction "VOUT_7") (pintype "power_in"))
    )
    (net (code "37") (name "VDD_12V0") (class "Default")
      (node (ref "C46") (pin "1") (pinfunction "1_1") (pintype "passive"))
      (node (ref "C47") (pin "1") (pinfunction "1_1") (pintype "passive"))
      (node (ref "C48") (pin "1") (pinfunction "1_1") (pintype "passive"))
      (node (ref "C49") (pin "1") (pinfunction "1_1") (pintype "passive"))
      (node (ref "C50") (pin "2") (pinfunction "2_2") (pintype "passive"))
      (node (ref "C51") (pin "2") (pinfunction "2_2") (pintype "passive"))
      (node (ref "R115") (pin "1") (pinfunction "1_1") (pintype "passive"))
      (node (ref "U15") (pin "7") (pinfunction "VOUT_7") (pintype "power_in"))
    )
  )
)
